# USB-Switch.net
KiCad netlist of a schematic drawn in Altium Designer
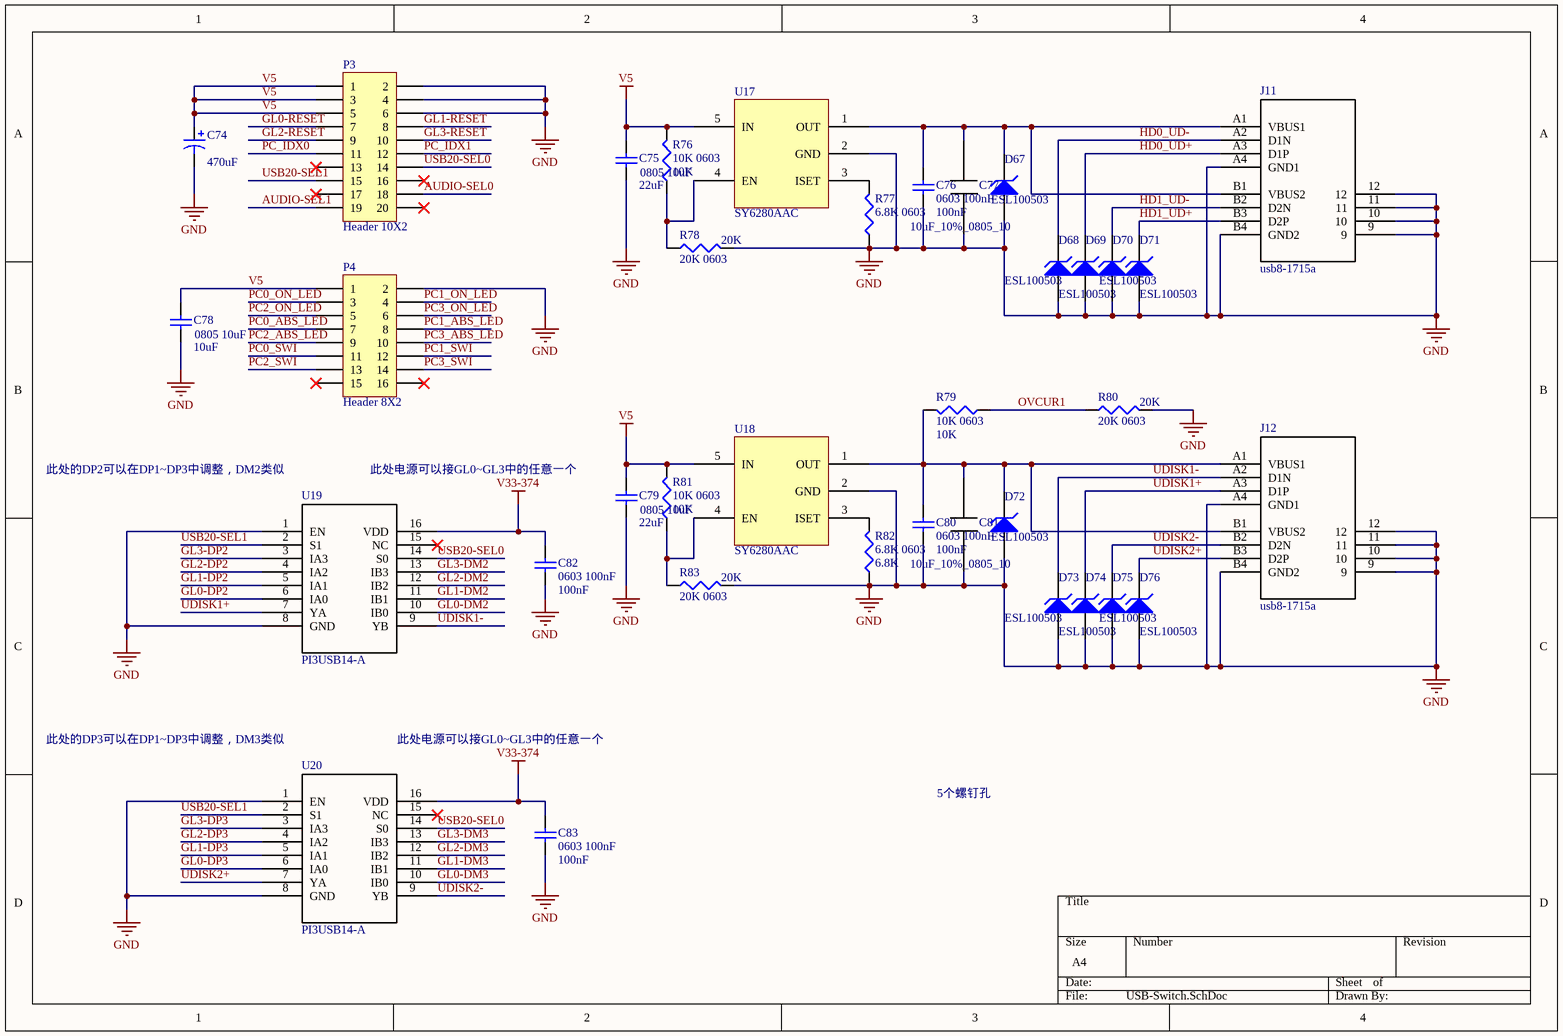
[diagram p0: USB-Switch.SchDoc]

(export (version "E")
  (design (tool "Eeschema 10.0.6"))
  (components
    (comp (ref "C74")
      (value "470uF")
      (footprint "RB7_6-15")
      (description "Polarized Capacitor (Radial)")
      (fields (field (name "PUBLISHER") "Altium Limited"))
      (libsource (lib "Miscellaneous Devices") (part "Cap Pol1"))
    )
    (comp (ref "C75")
      (value "0805 10uF")
      (footprint "C0805")
      (description "Capacitor (Semiconductor SIM Model)")
      (fields (field (name "ALTIUM_VALUE") "22uF") (field (name "PUBLISHER") "Altium Limited"))
      (libsource (lib "Miscellaneous Devices") (part "Cap Semi"))
    )
    (comp (ref "C76")
      (value "0603 100nF")
      (footprint "C0603")
      (description "Capacitor (Semiconductor SIM Model)")
      (fields (field (name "ALTIUM_VALUE") "100nF") (field (name "PUBLISHER") "Altium Limited"))
      (libsource (lib "Miscellaneous Devices") (part "Cap Semi"))
    )
    (comp (ref "C77")
      (value "10uF_10%_0805_10")
      (footprint "C0805")
      (description "Imported")
      (fields (field (name "DESIGNER") "Chiphome"))
      (libsource (lib "cap-0805-ca") (part "10uF_10%_0805_10"))
    )
    (comp (ref "C78")
      (value "0805 10uF")
      (footprint "C0805")
      (description "Capacitor (Semiconductor SIM Model)")
      (fields (field (name "ALTIUM_VALUE") "10uF") (field (name "PUBLISHER") "Altium Limited"))
      (libsource (lib "Miscellaneous Devices") (part "Cap Semi"))
    )
    (comp (ref "C79")
      (value "0805 10uF")
      (footprint "C0805")
      (description "Capacitor (Semiconductor SIM Model)")
      (fields (field (name "ALTIUM_VALUE") "22uF") (field (name "PUBLISHER") "Altium Limited"))
      (libsource (lib "Miscellaneous Devices") (part "Cap Semi"))
    )
    (comp (ref "C80")
      (value "0603 100nF")
      (footprint "C0603")
      (description "Capacitor (Semiconductor SIM Model)")
      (fields (field (name "ALTIUM_VALUE") "100nF") (field (name "PUBLISHER") "Altium Limited"))
      (libsource (lib "Miscellaneous Devices") (part "Cap Semi"))
    )
    (comp (ref "C81")
      (value "10uF_10%_0805_10")
      (footprint "C0805")
      (description "Imported")
      (fields (field (name "DESIGNER") "Chiphome"))
      (libsource (lib "cap-0805-ca") (part "10uF_10%_0805_10"))
    )
    (comp (ref "C82")
      (value "0603 100nF")
      (footprint "C0603")
      (description "Capacitor (Semiconductor SIM Model)")
      (fields (field (name "ALTIUM_VALUE") "100nF") (field (name "PUBLISHER") "Altium Limited"))
      (libsource (lib "Miscellaneous Devices") (part "Cap Semi"))
    )
    (comp (ref "C83")
      (value "0603 100nF")
      (footprint "C0603")
      (description "Capacitor (Semiconductor SIM Model)")
      (fields (field (name "ALTIUM_VALUE") "100nF") (field (name "PUBLISHER") "Altium Limited"))
      (libsource (lib "Miscellaneous Devices") (part "Cap Semi"))
    )
    (comp (ref "D67")
      (value "ESL100503")
      (footprint "C0402")
      (fields (field (name "PUBLISHER") "Altium Limited"))
      (libsource (lib "Miscellaneous Devices") (part "D Zener"))
    )
    (comp (ref "D68")
      (value "ESL100503")
      (footprint "C0402")
      (fields (field (name "PUBLISHER") "Altium Limited"))
      (libsource (lib "Miscellaneous Devices") (part "D Zener"))
    )
    (comp (ref "D69")
      (value "ESL100503")
      (footprint "C0402")
      (fields (field (name "PUBLISHER") "Altium Limited"))
      (libsource (lib "Miscellaneous Devices") (part "D Zener"))
    )
    (comp (ref "D70")
      (value "ESL100503")
      (footprint "C0402")
      (fields (field (name "PUBLISHER") "Altium Limited"))
      (libsource (lib "Miscellaneous Devices") (part "D Zener"))
    )
    (comp (ref "D71")
      (value "ESL100503")
      (footprint "C0402")
      (fields (field (name "PUBLISHER") "Altium Limited"))
      (libsource (lib "Miscellaneous Devices") (part "D Zener"))
    )
    (comp (ref "D72")
      (value "ESL100503")
      (footprint "C0402")
      (fields (field (name "PUBLISHER") "Altium Limited"))
      (libsource (lib "Miscellaneous Devices") (part "D Zener"))
    )
    (comp (ref "D73")
      (value "ESL100503")
      (footprint "C0402")
      (fields (field (name "PUBLISHER") "Altium Limited"))
      (libsource (lib "Miscellaneous Devices") (part "D Zener"))
    )
    (comp (ref "D74")
      (value "ESL100503")
      (footprint "C0402")
      (fields (field (name "PUBLISHER") "Altium Limited"))
      (libsource (lib "Miscellaneous Devices") (part "D Zener"))
    )
    (comp (ref "D75")
      (value "ESL100503")
      (footprint "C0402")
      (fields (field (name "PUBLISHER") "Altium Limited"))
      (libsource (lib "Miscellaneous Devices") (part "D Zener"))
    )
    (comp (ref "D76")
      (value "ESL100503")
      (footprint "C0402")
      (fields (field (name "PUBLISHER") "Altium Limited"))
      (libsource (lib "Miscellaneous Devices") (part "D Zener"))
    )
    (comp (ref "J11")
      (value "usb8-1715a")
      (footprint "usb8-1715a")
      (description "Imported")
      (libsource (lib "USBx2") (part "usb8-1715a"))
    )
    (comp (ref "J12")
      (value "usb8-1715a")
      (footprint "usb8-1715a")
      (description "Imported")
      (libsource (lib "USBx2") (part "usb8-1715a"))
    )
    (comp (ref "P3")
      (value "Header 10X2")
      (footprint "HDR2X10")
      (description "Header, 10-Pin, Dual row")
      (fields (field (name "PUBLISHER") "Altium Limited"))
      (libsource (lib "Common Headers") (part "Header 10X2"))
    )
    (comp (ref "P4")
      (value "Header 8X2")
      (footprint "HDR2X8")
      (description "Header, 8-Pin, Dual row")
      (fields (field (name "PUBLISHER") "Altium Limited"))
      (libsource (lib "Common Headers") (part "Header 8X2"))
    )
    (comp (ref "R76")
      (value "10K 0603")
      (footprint "R0603")
      (description "Resistor")
      (fields (field (name "ALTIUM_VALUE") "10K") (field (name "PUBLISHER") "Altium Limited"))
      (libsource (lib "Miscellaneous Devices") (part "Res3"))
    )
    (comp (ref "R77")
      (value "6.8K 0603")
      (footprint "R0603")
      (description "Resistor")
      (fields (field (name "PUBLISHER") "Altium Limited"))
      (libsource (lib "Miscellaneous Devices") (part "Res3"))
    )
    (comp (ref "R78")
      (value "20K 0603")
      (footprint "R0603")
      (description "Resistor")
      (fields (field (name "ALTIUM_VALUE") "20K") (field (name "PUBLISHER") "Altium Limited"))
      (libsource (lib "Miscellaneous Devices") (part "Res3"))
    )
    (comp (ref "R79")
      (value "10K 0603")
      (footprint "R0603")
      (description "Resistor")
      (fields (field (name "ALTIUM_VALUE") "10K") (field (name "PUBLISHER") "Altium Limited"))
      (libsource (lib "Miscellaneous Devices") (part "Res3"))
    )
    (comp (ref "R80")
      (value "20K 0603")
      (footprint "R0603")
      (description "Resistor")
      (fields (field (name "ALTIUM_VALUE") "20K") (field (name "PUBLISHER") "Altium Limited"))
      (libsource (lib "Miscellaneous Devices") (part "Res3"))
    )
    (comp (ref "R81")
      (value "10K 0603")
      (footprint "R0603")
      (description "Resistor")
      (fields (field (name "ALTIUM_VALUE") "10K") (field (name "PUBLISHER") "Altium Limited"))
      (libsource (lib "Miscellaneous Devices") (part "Res3"))
    )
    (comp (ref "R82")
      (value "6.8K 0603")
      (footprint "R0603")
      (description "Resistor")
      (fields (field (name "ALTIUM_VALUE") "6.8K") (field (name "PUBLISHER") "Altium Limited"))
      (libsource (lib "Miscellaneous Devices") (part "Res3"))
    )
    (comp (ref "R83")
      (value "20K 0603")
      (footprint "R0603")
      (description "Resistor")
      (fields (field (name "ALTIUM_VALUE") "20K") (field (name "PUBLISHER") "Altium Limited"))
      (libsource (lib "Miscellaneous Devices") (part "Res3"))
    )
    (comp (ref "U17")
      (value "SY6280AAC")
      (footprint "SOT23-5")
      (libsource (lib "SY6280AAC") (part "Component_1"))
    )
    (comp (ref "U18")
      (value "SY6280AAC")
      (footprint "SOT23-5")
      (libsource (lib "SY6280AAC") (part "Component_1"))
    )
    (comp (ref "U19")
      (value "PI3USB14-A")
      (footprint "sop16-26-064a")
      (description "Imported")
      (fields (field (name "DESIGNER") "Chiphome"))
      (libsource (lib "USB-new-component") (part "PI3USB14-A"))
    )
    (comp (ref "U20")
      (value "PI3USB14-A")
      (footprint "sop16-26-064a")
      (description "Imported")
      (fields (field (name "DESIGNER") "Chiphome"))
      (libsource (lib "USB-new-component") (part "PI3USB14-A"))
    )
  )
  (nets
    (net (code "1") (name "/AUDIO-SEL0") (class "Default")
      (node (ref "P3") (pin "18") (pinfunction "18_18") (pintype "passive"))
    )
    (net (code "2") (name "/AUDIO-SEL1") (class "Default")
      (node (ref "P3") (pin "19") (pinfunction "19_19") (pintype "passive"))
    )
    (net (code "3") (name "/GL0-DM2") (class "Default")
      (node (ref "U19") (pin "10") (pinfunction "IB0_10") (pintype "passive"))
    )
    (net (code "4") (name "/GL0-DM3") (class "Default")
      (node (ref "U20") (pin "10") (pinfunction "IB0_10") (pintype "passive"))
    )
    (net (code "5") (name "/GL0-DP2") (class "Default")
      (node (ref "U19") (pin "6") (pinfunction "IA0_6") (pintype "passive"))
    )
    (net (code "6") (name "/GL0-DP3") (class "Default")
      (node (ref "U20") (pin "6") (pinfunction "IA0_6") (pintype "passive"))
    )
    (net (code "7") (name "/GL0-RESET") (class "Default")
      (node (ref "P3") (pin "7") (pinfunction "7_7") (pintype "passive"))
    )
    (net (code "8") (name "/GL1-DM2") (class "Default")
      (node (ref "U19") (pin "11") (pinfunction "IB1_11") (pintype "passive"))
    )
    (net (code "9") (name "/GL1-DM3") (class "Default")
      (node (ref "U20") (pin "11") (pinfunction "IB1_11") (pintype "passive"))
    )
    (net (code "10") (name "/GL1-DP2") (class "Default")
      (node (ref "U19") (pin "5") (pinfunction "IA1_5") (pintype "passive"))
    )
    (net (code "11") (name "/GL1-DP3") (class "Default")
      (node (ref "U20") (pin "5") (pinfunction "IA1_5") (pintype "passive"))
    )
    (net (code "12") (name "/GL1-RESET") (class "Default")
      (node (ref "P3") (pin "8") (pinfunction "8_8") (pintype "passive"))
    )
    (net (code "13") (name "/GL2-DM2") (class "Default")
      (node (ref "U19") (pin "12") (pinfunction "IB2_12") (pintype "passive"))
    )
    (net (code "14") (name "/GL2-DM3") (class "Default")
      (node (ref "U20") (pin "12") (pinfunction "IB2_12") (pintype "passive"))
    )
    (net (code "15") (name "/GL2-DP2") (class "Default")
      (node (ref "U19") (pin "4") (pinfunction "IA2_4") (pintype "passive"))
    )
    (net (code "16") (name "/GL2-DP3") (class "Default")
      (node (ref "U20") (pin "4") (pinfunction "IA2_4") (pintype "passive"))
    )
    (net (code "17") (name "/GL2-RESET") (class "Default")
      (node (ref "P3") (pin "9") (pinfunction "9_9") (pintype "passive"))
    )
    (net (code "18") (name "/GL3-DM2") (class "Default")
      (node (ref "U19") (pin "13") (pinfunction "IB3_13") (pintype "passive"))
    )
    (net (code "19") (name "/GL3-DM3") (class "Default")
      (node (ref "U20") (pin "13") (pinfunction "IB3_13") (pintype "passive"))
    )
    (net (code "20") (name "/GL3-DP2") (class "Default")
      (node (ref "U19") (pin "3") (pinfunction "IA3_3") (pintype "passive"))
    )
    (net (code "21") (name "/GL3-DP3") (class "Default")
      (node (ref "U20") (pin "3") (pinfunction "IA3_3") (pintype "passive"))
    )
    (net (code "22") (name "/GL3-RESET") (class "Default")
      (node (ref "P3") (pin "10") (pinfunction "10_10") (pintype "passive"))
    )
    (net (code "23") (name "/HD0_UD+") (class "Default")
      (node (ref "D69") (pin "2") (pinfunction "K_2") (pintype "passive"))
      (node (ref "J11") (pin "A3") (pinfunction "D1P_A3") (pintype "passive"))
    )
    (net (code "24") (name "/HD0_UD-") (class "Default")
      (node (ref "D68") (pin "2") (pinfunction "K_2") (pintype "passive"))
      (node (ref "J11") (pin "A2") (pinfunction "D1N_A2") (pintype "passive"))
    )
    (net (code "25") (name "/HD1_UD+") (class "Default")
      (node (ref "D71") (pin "2") (pinfunction "K_2") (pintype "passive"))
      (node (ref "J11") (pin "B3") (pinfunction "D2P_B3") (pintype "passive"))
    )
    (net (code "26") (name "/HD1_UD-") (class "Default")
      (node (ref "D70") (pin "2") (pinfunction "K_2") (pintype "passive"))
      (node (ref "J11") (pin "B2") (pinfunction "D2N_B2") (pintype "passive"))
    )
    (net (code "27") (name "/OVCUR1") (class "Default")
      (node (ref "R79") (pin "1") (pinfunction "1_1") (pintype "passive"))
      (node (ref "R80") (pin "1") (pinfunction "1_1") (pintype "passive"))
    )
    (net (code "28") (name "/PC0_ABS_LED") (class "Default")
      (node (ref "P4") (pin "7") (pinfunction "7_7") (pintype "passive"))
    )
    (net (code "29") (name "/PC0_ON_LED") (class "Default")
      (node (ref "P4") (pin "3") (pinfunction "3_3") (pintype "passive"))
    )
    (net (code "30") (name "/PC0_SWI") (class "Default")
      (node (ref "P4") (pin "11") (pinfunction "11_11") (pintype "passive"))
    )
    (net (code "31") (name "/PC1_ABS_LED") (class "Default")
      (node (ref "P4") (pin "8") (pinfunction "8_8") (pintype "passive"))
    )
    (net (code "32") (name "/PC1_ON_LED") (class "Default")
      (node (ref "P4") (pin "4") (pinfunction "4_4") (pintype "passive"))
    )
    (net (code "33") (name "/PC1_SWI") (class "Default")
      (node (ref "P4") (pin "12") (pinfunction "12_12") (pintype "passive"))
    )
    (net (code "34") (name "/PC2_ABS_LED") (class "Default")
      (node (ref "P4") (pin "9") (pinfunction "9_9") (pintype "passive"))
    )
    (net (code "35") (name "/PC2_ON_LED") (class "Default")
      (node (ref "P4") (pin "5") (pinfunction "5_5") (pintype "passive"))
    )
    (net (code "36") (name "/PC2_SWI") (class "Default")
      (node (ref "P4") (pin "13") (pinfunction "13_13") (pintype "passive"))
    )
    (net (code "37") (name "/PC3_ABS_LED") (class "Default")
      (node (ref "P4") (pin "10") (pinfunction "10_10") (pintype "passive"))
    )
    (net (code "38") (name "/PC3_ON_LED") (class "Default")
      (node (ref "P4") (pin "6") (pinfunction "6_6") (pintype "passive"))
    )
    (net (code "39") (name "/PC3_SWI") (class "Default")
      (node (ref "P4") (pin "14") (pinfunction "14_14") (pintype "passive"))
    )
    (net (code "40") (name "/PC_IDX0") (class "Default")
      (node (ref "P3") (pin "11") (pinfunction "11_11") (pintype "passive"))
    )
    (net (code "41") (name "/PC_IDX1") (class "Default")
      (node (ref "P3") (pin "12") (pinfunction "12_12") (pintype "passive"))
    )
    (net (code "42") (name "/UDISK1+") (class "Default")
      (node (ref "D74") (pin "2") (pinfunction "K_2") (pintype "passive"))
      (node (ref "J12") (pin "A3") (pinfunction "D1P_A3") (pintype "passive"))
      (node (ref "U19") (pin "7") (pinfunction "YA_7") (pintype "passive"))
    )
    (net (code "43") (name "/UDISK1-") (class "Default")
      (node (ref "D73") (pin "2") (pinfunction "K_2") (pintype "passive"))
      (node (ref "J12") (pin "A2") (pinfunction "D1N_A2") (pintype "passive"))
      (node (ref "U19") (pin "9") (pinfunction "YB_9") (pintype "passive"))
    )
    (net (code "44") (name "/UDISK2+") (class "Default")
      (node (ref "D76") (pin "2") (pinfunction "K_2") (pintype "passive"))
      (node (ref "J12") (pin "B3") (pinfunction "D2P_B3") (pintype "passive"))
      (node (ref "U20") (pin "7") (pinfunction "YA_7") (pintype "passive"))
    )
    (net (code "45") (name "/UDISK2-") (class "Default")
      (node (ref "D75") (pin "2") (pinfunction "K_2") (pintype "passive"))
      (node (ref "J12") (pin "B2") (pinfunction "D2N_B2") (pintype "passive"))
      (node (ref "U20") (pin "9") (pinfunction "YB_9") (pintype "passive"))
    )
    (net (code "46") (name "/USB20-SEL0") (class "Default")
      (node (ref "P3") (pin "14") (pinfunction "14_14") (pintype "passive"))
      (node (ref "U19") (pin "14") (pinfunction "S0_14") (pintype "passive"))
      (node (ref "U20") (pin "14") (pinfunction "S0_14") (pintype "passive"))
    )
    (net (code "47") (name "/USB20-SEL1") (class "Default")
      (node (ref "P3") (pin "15") (pinfunction "15_15") (pintype "passive"))
      (node (ref "U19") (pin "2") (pinfunction "S1_2") (pintype "passive"))
      (node (ref "U20") (pin "2") (pinfunction "S1_2") (pintype "passive"))
    )
    (net (code "48") (name "GND") (class "Default")
      (node (ref "C74") (pin "2") (pinfunction "2_2") (pintype "passive"))
      (node (ref "C75") (pin "1") (pinfunction "1_1") (pintype "passive"))
      (node (ref "C76") (pin "1") (pinfunction "1_1") (pintype "passive"))
      (node (ref "C77") (pin "1") (pinfunction "1_1") (pintype "passive"))
      (node (ref "C78") (pin "1") (pinfunction "1_1") (pintype "passive"))
      (node (ref "C79") (pin "1") (pinfunction "1_1") (pintype "passive"))
      (node (ref "C80") (pin "1") (pinfunction "1_1") (pintype "passive"))
      (node (ref "C81") (pin "1") (pinfunction "1_1") (pintype "passive"))
      (node (ref "C82") (pin "1") (pinfunction "1_1") (pintype "passive"))
      (node (ref "C83") (pin "1") (pinfunction "1_1") (pintype "passive"))
      (node (ref "D67") (pin "1") (pinfunction "A_1") (pintype "passive"))
      (node (ref "D68") (pin "1") (pinfunction "A_1") (pintype "passive"))
      (node (ref "D69") (pin "1") (pinfunction "A_1") (pintype "passive"))
      (node (ref "D70") (pin "1") (pinfunction "A_1") (pintype "passive"))
      (node (ref "D71") (pin "1") (pinfunction "A_1") (pintype "passive"))
      (node (ref "D72") (pin "1") (pinfunction "A_1") (pintype "passive"))
      (node (ref "D73") (pin "1") (pinfunction "A_1") (pintype "passive"))
      (node (ref "D74") (pin "1") (pinfunction "A_1") (pintype "passive"))
      (node (ref "D75") (pin "1") (pinfunction "A_1") (pintype "passive"))
      (node (ref "D76") (pin "1") (pinfunction "A_1") (pintype "passive"))
      (node (ref "J11") (pin "10") (pinfunction "10_10") (pintype "passive"))
      (node (ref "J11") (pin "11") (pinfunction "11_11") (pintype "passive"))
      (node (ref "J11") (pin "12") (pinfunction "12_12") (pintype "passive"))
      (node (ref "J11") (pin "9") (pinfunction "9_9") (pintype "passive"))
      (node (ref "J11") (pin "A4") (pinfunction "GND1_A4") (pintype "passive"))
      (node (ref "J11") (pin "B4") (pinfunction "GND2_B4") (pintype "passive"))
      (node (ref "J12") (pin "10") (pinfunction "10_10") (pintype "passive"))
      (node (ref "J12") (pin "11") (pinfunction "11_11") (pintype "passive"))
      (node (ref "J12") (pin "12") (pinfunction "12_12") (pintype "passive"))
      (node (ref "J12") (pin "9") (pinfunction "9_9") (pintype "passive"))
      (node (ref "J12") (pin "A4") (pinfunction "GND1_A4") (pintype "passive"))
      (node (ref "J12") (pin "B4") (pinfunction "GND2_B4") (pintype "passive"))
      (node (ref "P3") (pin "2") (pinfunction "2_2") (pintype "passive"))
      (node (ref "P3") (pin "4") (pinfunction "4_4") (pintype "passive"))
      (node (ref "P3") (pin "6") (pinfunction "6_6") (pintype "passive"))
      (node (ref "P4") (pin "2") (pinfunction "2_2") (pintype "passive"))
      (node (ref "R77") (pin "1") (pinfunction "1_1") (pintype "passive"))
      (node (ref "R78") (pin "2") (pinfunction "2_2") (pintype "passive"))
      (node (ref "R80") (pin "2") (pinfunction "2_2") (pintype "passive"))
      (node (ref "R82") (pin "1") (pinfunction "1_1") (pintype "passive"))
      (node (ref "R83") (pin "2") (pinfunction "2_2") (pintype "passive"))
      (node (ref "U17") (pin "2") (pinfunction "GND_2") (pintype "passive"))
      (node (ref "U18") (pin "2") (pinfunction "GND_2") (pintype "passive"))
      (node (ref "U19") (pin "1") (pinfunction "EN_1") (pintype "passive"))
      (node (ref "U19") (pin "8") (pinfunction "GND_8") (pintype "passive"))
      (node (ref "U20") (pin "1") (pinfunction "EN_1") (pintype "passive"))
      (node (ref "U20") (pin "8") (pinfunction "GND_8") (pintype "passive"))
    )
    (net (code "49") (name "Net-(D67-K)") (class "Default")
      (node (ref "C76") (pin "2") (pinfunction "2_2") (pintype "passive"))
      (node (ref "C77") (pin "2") (pinfunction "2_2") (pintype "passive"))
      (node (ref "D67") (pin "2") (pinfunction "K_2") (pintype "passive"))
      (node (ref "J11") (pin "A1") (pinfunction "VBUS1_A1") (pintype "passive"))
      (node (ref "J11") (pin "B1") (pinfunction "VBUS2_B1") (pintype "passive"))
      (node (ref "U17") (pin "1") (pinfunction "OUT_1") (pintype "passive"))
    )
    (net (code "50") (name "Net-(D72-K)") (class "Default")
      (node (ref "C80") (pin "2") (pinfunction "2_2") (pintype "passive"))
      (node (ref "C81") (pin "2") (pinfunction "2_2") (pintype "passive"))
      (node (ref "D72") (pin "2") (pinfunction "K_2") (pintype "passive"))
      (node (ref "J12") (pin "A1") (pinfunction "VBUS1_A1") (pintype "passive"))
      (node (ref "J12") (pin "B1") (pinfunction "VBUS2_B1") (pintype "passive"))
      (node (ref "R79") (pin "2") (pinfunction "2_2") (pintype "passive"))
      (node (ref "U18") (pin "1") (pinfunction "OUT_1") (pintype "passive"))
    )
    (net (code "51") (name "Net-(U17-EN)") (class "Default")
      (node (ref "R76") (pin "1") (pinfunction "1_1") (pintype "passive"))
      (node (ref "R78") (pin "1") (pinfunction "1_1") (pintype "passive"))
      (node (ref "U17") (pin "4") (pinfunction "EN_4") (pintype "passive"))
    )
    (net (code "52") (name "Net-(U17-ISET)") (class "Default")
      (node (ref "R77") (pin "2") (pinfunction "2_2") (pintype "passive"))
      (node (ref "U17") (pin "3") (pinfunction "ISET_3") (pintype "passive"))
    )
    (net (code "53") (name "Net-(U18-EN)") (class "Default")
      (node (ref "R81") (pin "1") (pinfunction "1_1") (pintype "passive"))
      (node (ref "R83") (pin "1") (pinfunction "1_1") (pintype "passive"))
      (node (ref "U18") (pin "4") (pinfunction "EN_4") (pintype "passive"))
    )
    (net (code "54") (name "Net-(U18-ISET)") (class "Default")
      (node (ref "R82") (pin "2") (pinfunction "2_2") (pintype "passive"))
      (node (ref "U18") (pin "3") (pinfunction "ISET_3") (pintype "passive"))
    )
    (net (code "55") (name "V5") (class "Default")
      (node (ref "C74") (pin "1") (pinfunction "1_1") (pintype "passive"))
      (node (ref "C75") (pin "2") (pinfunction "2_2") (pintype "passive"))
      (node (ref "C78") (pin "2") (pinfunction "2_2") (pintype "passive"))
      (node (ref "C79") (pin "2") (pinfunction "2_2") (pintype "passive"))
      (node (ref "P3") (pin "1") (pinfunction "1_1") (pintype "passive"))
      (node (ref "P3") (pin "3") (pinfunction "3_3") (pintype "passive"))
      (node (ref "P3") (pin "5") (pinfunction "5_5") (pintype "passive"))
      (node (ref "P4") (pin "1") (pinfunction "1_1") (pintype "passive"))
      (node (ref "R76") (pin "2") (pinfunction "2_2") (pintype "passive"))
      (node (ref "R81") (pin "2") (pinfunction "2_2") (pintype "passive"))
      (node (ref "U17") (pin "5") (pinfunction "IN_5") (pintype "passive"))
      (node (ref "U18") (pin "5") (pinfunction "IN_5") (pintype "passive"))
    )
    (net (code "56") (name "V33-374") (class "Default")
      (node (ref "C82") (pin "2") (pinfunction "2_2") (pintype "passive"))
      (node (ref "C83") (pin "2") (pinfunction "2_2") (pintype "passive"))
      (node (ref "U19") (pin "16") (pinfunction "VDD_16") (pintype "passive"))
      (node (ref "U20") (pin "16") (pinfunction "VDD_16") (pintype "passive"))
    )
    (net (code "57") (name "unconnected-(P3-Pad13)") (class "Default")
      (node (ref "P3") (pin "13") (pinfunction "13_13") (pintype "passive+no_connect"))
    )
    (net (code "58") (name "unconnected-(P3-Pad16)") (class "Default")
      (node (ref "P3") (pin "16") (pinfunction "16_16") (pintype "passive+no_connect"))
    )
    (net (code "59") (name "unconnected-(P3-Pad17)") (class "Default")
      (node (ref "P3") (pin "17") (pinfunction "17_17") (pintype "passive+no_connect"))
    )
    (net (code "60") (name "unconnected-(P3-Pad20)") (class "Default")
      (node (ref "P3") (pin "20") (pinfunction "20_20") (pintype "passive+no_connect"))
    )
    (net (code "61") (name "unconnected-(P4-Pad15)") (class "Default")
      (node (ref "P4") (pin "15") (pinfunction "15_15") (pintype "passive+no_connect"))
    )
    (net (code "62") (name "unconnected-(P4-Pad16)") (class "Default")
      (node (ref "P4") (pin "16") (pinfunction "16_16") (pintype "passive+no_connect"))
    )
    (net (code "63") (name "unconnected-(U19-NC-Pad15)") (class "Default")
      (node (ref "U19") (pin "15") (pinfunction "NC_15") (pintype "passive+no_connect"))
    )
    (net (code "64") (name "unconnected-(U20-NC-Pad15)") (class "Default")
      (node (ref "U20") (pin "15") (pinfunction "NC_15") (pintype "passive+no_connect"))
    )
  )
)
